# test.net
KiCad netlist of a schematic drawn in Altium Designer
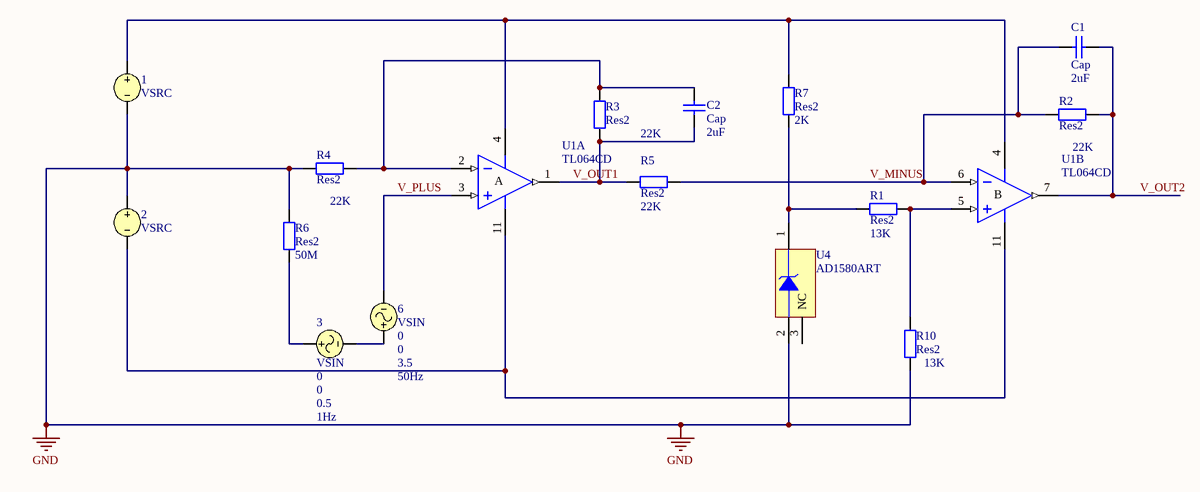
[diagram p0: test.SchDoc]

(export (version "E")
  (design (tool "Eeschema 10.0.6"))
  (components
    (comp (ref "1")
      (value "VSRC")
      (description "Voltage Source")
      (fields (field (name "PUBLISHER") "Altium Limited"))
      (libsource (lib "Simulation Sources") (part "VSRC"))
    )
    (comp (ref "2")
      (value "VSRC")
      (description "Voltage Source")
      (fields (field (name "PUBLISHER") "Altium Limited"))
      (libsource (lib "Simulation Sources") (part "VSRC"))
    )
    (comp (ref "3")
      (value "VSIN")
      (description "Sinusoidal Voltage Source")
      (fields
        (field (name "ALTIUM_VALUE") "0")
        (field (name "OFFSET") "0")
        (field (name "AMPLITUDE") "0.5")
        (field (name "FREQUENCY") "1Hz")
        (field (name "PUBLISHER") "Altium Limited")
      )
      (libsource (lib "Simulation Sources") (part "VSIN"))
    )
    (comp (ref "6")
      (value "VSIN")
      (description "Sinusoidal Voltage Source")
      (fields
        (field (name "ALTIUM_VALUE") "0")
        (field (name "OFFSET") "0")
        (field (name "AMPLITUDE") "3.5")
        (field (name "FREQUENCY") "50Hz")
        (field (name "PUBLISHER") "Altium Limited")
      )
      (libsource (lib "Simulation Sources") (part "VSIN"))
    )
    (comp (ref "C1")
      (value "Cap")
      (footprint "RAD-0.3")
      (description "Capacitor")
      (fields (field (name "ALTIUM_VALUE") "2uF") (field (name "PUBLISHER") "Altium Limited"))
      (libsource (lib "Miscellaneous Devices") (part "Cap"))
    )
    (comp (ref "C2")
      (value "Cap")
      (footprint "RAD-0.3")
      (description "Capacitor")
      (fields (field (name "ALTIUM_VALUE") "2uF") (field (name "PUBLISHER") "Altium Limited"))
      (libsource (lib "Miscellaneous Devices") (part "Cap"))
    )
    (comp (ref "R1")
      (value "Res2")
      (footprint "AXIAL-0.4")
      (description "Resistor")
      (fields (field (name "ALTIUM_VALUE") "13K") (field (name "PUBLISHER") "Altium Limited"))
      (libsource (lib "") (part "Res2_1"))
    )
    (comp (ref "R2")
      (value "Res2")
      (footprint "AXIAL-0.4")
      (description "Resistor")
      (fields (field (name "ALTIUM_VALUE") "22K") (field (name "PUBLISHER") "Altium Limited"))
      (libsource (lib "") (part "Res2_1"))
    )
    (comp (ref "R3")
      (value "Res2")
      (footprint "AXIAL-0.4")
      (description "Resistor")
      (fields (field (name "ALTIUM_VALUE") "22K") (field (name "PUBLISHER") "Altium Limited"))
      (libsource (lib "Miscellaneous Devices") (part "Res2"))
    )
    (comp (ref "R4")
      (value "Res2")
      (footprint "AXIAL-0.4")
      (description "Resistor")
      (fields (field (name "ALTIUM_VALUE") "22K") (field (name "PUBLISHER") "Altium Limited"))
      (libsource (lib "") (part "Res2_2"))
    )
    (comp (ref "R5")
      (value "Res2")
      (footprint "AXIAL-0.4")
      (description "Resistor")
      (fields (field (name "ALTIUM_VALUE") "22K") (field (name "PUBLISHER") "Altium Limited"))
      (libsource (lib "") (part "Res2_1"))
    )
    (comp (ref "R6")
      (value "Res2")
      (footprint "AXIAL-0.4")
      (description "Resistor")
      (fields (field (name "ALTIUM_VALUE") "50M") (field (name "PUBLISHER") "Altium Limited"))
      (libsource (lib "Miscellaneous Devices") (part "Res2"))
    )
    (comp (ref "R7")
      (value "Res2")
      (footprint "AXIAL-0.4")
      (description "Resistor")
      (fields (field (name "ALTIUM_VALUE") "2K") (field (name "PUBLISHER") "Altium Limited"))
      (libsource (lib "Miscellaneous Devices") (part "Res2"))
    )
    (comp (ref "R10")
      (value "Res2")
      (footprint "AXIAL-0.4")
      (description "Resistor")
      (fields (field (name "ALTIUM_VALUE") "13K") (field (name "PUBLISHER") "Altium Limited"))
      (libsource (lib "Miscellaneous Devices") (part "Res2"))
    )
    (comp (ref "U1")
      (value "TL064CD")
      (footprint "SO14_N")
      (description "Low-Power J-FET Quad Operational Amplifier")
      (fields (field (name "PUBLISHER") "Altium Limited"))
      (libsource (lib "ST Operational Amplifier") (part "TL064CD"))
    )
    (comp (ref "U4")
      (value "AD1580ART")
      (footprint "RT-3_N")
      (description "1.2V Micropower, Precision Shunt Voltage Reference")
      (fields (field (name "PUBLISHER") "Altium Limited"))
      (libsource (lib "AD Power Mgt Voltage Reference") (part "AD1580ART"))
    )
  )
  (nets
    (net (code "1") (name "/V_MINUS") (class "Default")
      (node (ref "C1") (pin "2") (pinfunction "2_2") (pintype "passive"))
      (node (ref "R2") (pin "2") (pinfunction "2_2") (pintype "passive"))
      (node (ref "R5") (pin "1") (pinfunction "1_1") (pintype "passive"))
      (node (ref "U1") (pin "6") (pinfunction "IN-_6") (pintype "input"))
    )
    (net (code "2") (name "/V_OUT1") (class "Default")
      (node (ref "C2") (pin "2") (pinfunction "2_2") (pintype "passive"))
      (node (ref "R3") (pin "1") (pinfunction "1_1") (pintype "passive"))
      (node (ref "R5") (pin "2") (pinfunction "2_2") (pintype "passive"))
      (node (ref "U1") (pin "1") (pinfunction "OUT_1") (pintype "output"))
    )
    (net (code "3") (name "/V_OUT2") (class "Default")
      (node (ref "C1") (pin "1") (pinfunction "1_1") (pintype "passive"))
      (node (ref "R2") (pin "1") (pinfunction "1_1") (pintype "passive"))
      (node (ref "U1") (pin "7") (pinfunction "OUT_7") (pintype "output"))
    )
    (net (code "4") (name "/V_PLUS") (class "Default")
      (node (ref "6") (pin "2") (pinfunction "2_2") (pintype "passive"))
      (node (ref "U1") (pin "3") (pinfunction "IN+_3") (pintype "input"))
    )
    (net (code "5") (name "GND") (class "Default")
      (node (ref "1") (pin "2") (pinfunction "2_2") (pintype "passive"))
      (node (ref "2") (pin "1") (pinfunction "1_1") (pintype "passive"))
      (node (ref "R10") (pin "1") (pinfunction "1_1") (pintype "passive"))
      (node (ref "R4") (pin "1") (pinfunction "1_1") (pintype "passive"))
      (node (ref "R6") (pin "2") (pinfunction "2_2") (pintype "passive"))
      (node (ref "U4") (pin "2") (pinfunction "V-_2") (pintype "power_in"))
    )
    (net (code "6") (name "Net-(3-Pad1)") (class "Default")
      (node (ref "3") (pin "1") (pinfunction "1_1") (pintype "passive"))
      (node (ref "R6") (pin "1") (pinfunction "1_1") (pintype "passive"))
    )
    (net (code "7") (name "Net-(3-Pad2)") (class "Default")
      (node (ref "3") (pin "2") (pinfunction "2_2") (pintype "passive"))
      (node (ref "6") (pin "1") (pinfunction "1_1") (pintype "passive"))
    )
    (net (code "8") (name "Net-(U1A-IN-)") (class "Default")
      (node (ref "C2") (pin "1") (pinfunction "1_1") (pintype "passive"))
      (node (ref "R3") (pin "2") (pinfunction "2_2") (pintype "passive"))
      (node (ref "R4") (pin "2") (pinfunction "2_2") (pintype "passive"))
      (node (ref "U1") (pin "2") (pinfunction "IN-_2") (pintype "input"))
    )
    (net (code "9") (name "Net-(U1A-V+)") (class "Default")
      (node (ref "1") (pin "1") (pinfunction "1_1") (pintype "passive"))
      (node (ref "R7") (pin "2") (pinfunction "2_2") (pintype "passive"))
      (node (ref "U1") (pin "4") (pinfunction "V+_4") (pintype "power_in"))
    )
    (net (code "10") (name "Net-(U1A-V-)") (class "Default")
      (node (ref "2") (pin "2") (pinfunction "2_2") (pintype "passive"))
      (node (ref "U1") (pin "11") (pinfunction "V-_11") (pintype "power_in"))
    )
    (net (code "11") (name "Net-(U1B-IN+)") (class "Default")
      (node (ref "R1") (pin "1") (pinfunction "1_1") (pintype "passive"))
      (node (ref "R10") (pin "2") (pinfunction "2_2") (pintype "passive"))
      (node (ref "U1") (pin "5") (pinfunction "IN+_5") (pintype "input"))
    )
    (net (code "12") (name "Net-(U4-V+)") (class "Default")
      (node (ref "R1") (pin "2") (pinfunction "2_2") (pintype "passive"))
      (node (ref "R7") (pin "1") (pinfunction "1_1") (pintype "passive"))
      (node (ref "U4") (pin "1") (pinfunction "V+_1") (pintype "power_in"))
    )
    (net (code "13") (name "unconnected-(U4-NC-Pad3)") (class "Default")
      (node (ref "U4") (pin "3") (pinfunction "NC_3") (pintype "passive"))
    )
  )
)
